# KegWasher_1_5_Schematic.net
KiCad netlist of a schematic drawn in EasyEDA
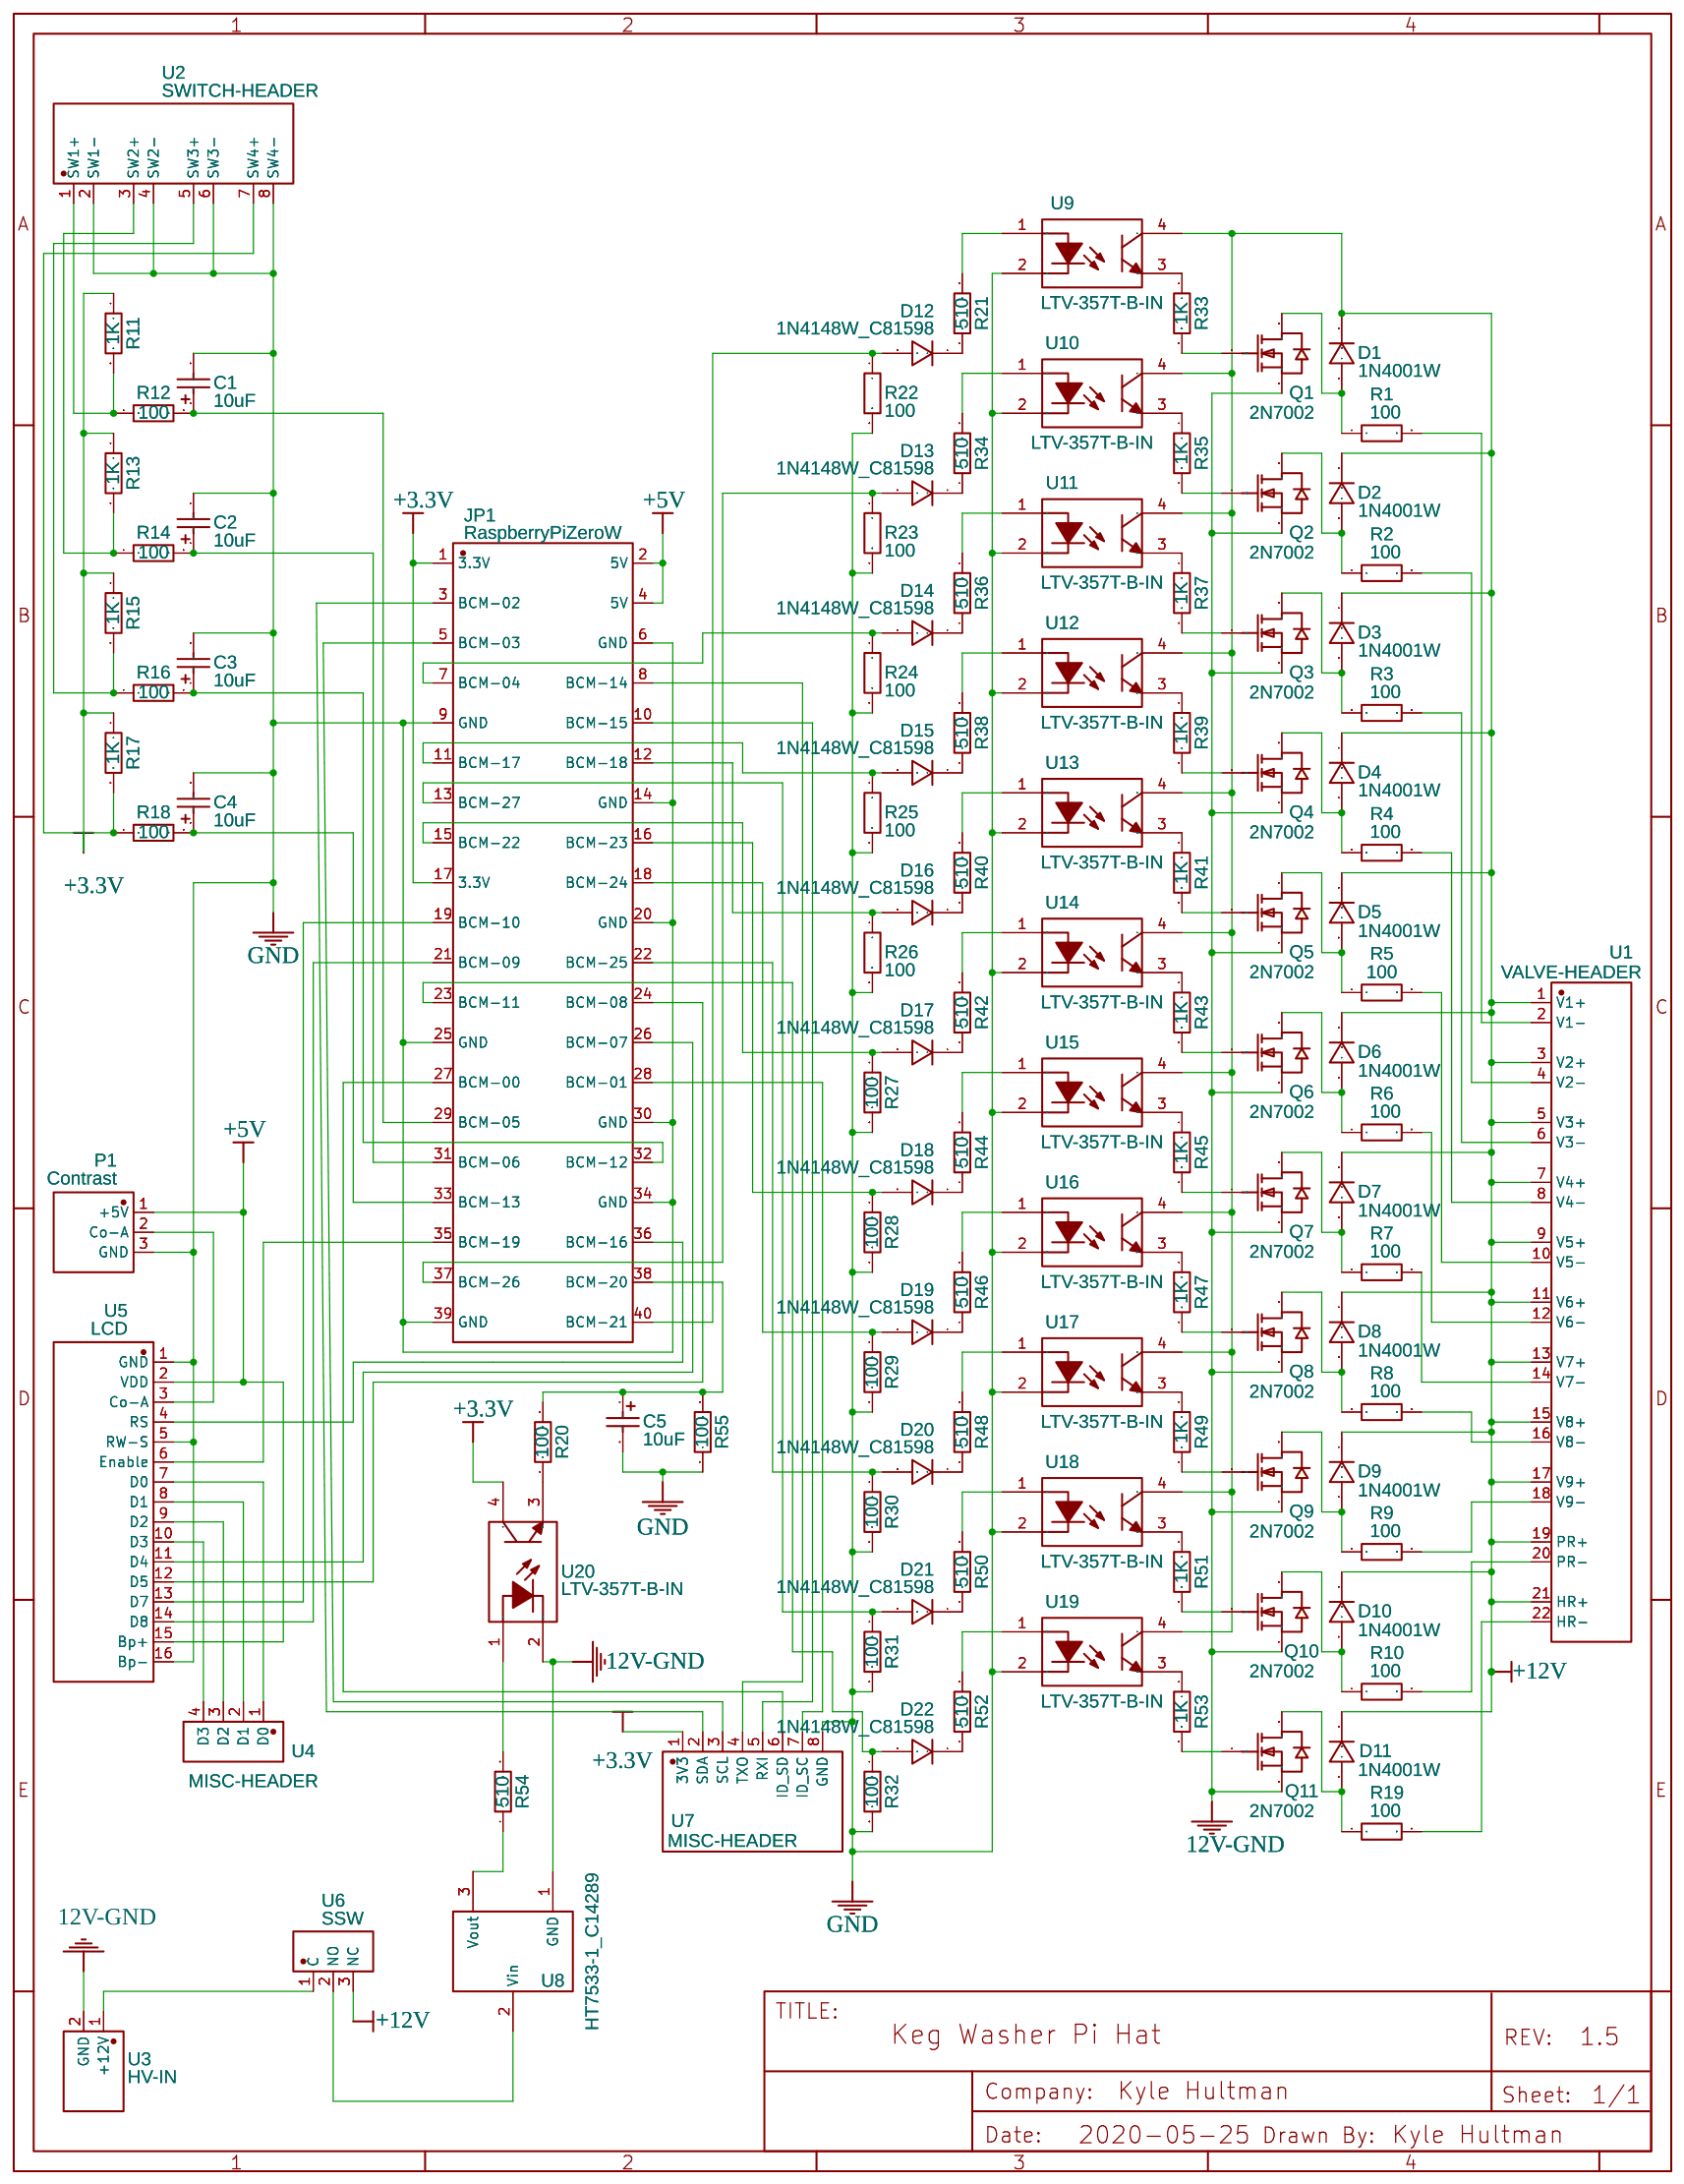
[diagram p0: schematic sheet]

(export (version "E")
  (design (tool "Eeschema 10.0.6"))
  (components
    (comp (ref "C1")
      (value "10uF")
      (fields
        (field (name "BOM_Manufacturer Part") "TAJA106K016RNJ")
        (field (name "BOM_Supplier Part") "C7171")
      )
      (libsource (lib "") (part "TAJA106K016RNJ"))
    )
    (comp (ref "C2")
      (value "10uF")
      (fields
        (field (name "BOM_Manufacturer Part") "TAJA106K016RNJ")
        (field (name "BOM_Supplier Part") "C7171")
      )
      (libsource (lib "") (part "TAJA106K016RNJ"))
    )
    (comp (ref "C3")
      (value "10uF")
      (fields
        (field (name "BOM_Manufacturer Part") "TAJA106K016RNJ")
        (field (name "BOM_Supplier Part") "C7171")
      )
      (libsource (lib "") (part "TAJA106K016RNJ"))
    )
    (comp (ref "C4")
      (value "10uF")
      (fields
        (field (name "BOM_Manufacturer Part") "TAJA106K016RNJ")
        (field (name "BOM_Supplier Part") "C7171")
      )
      (libsource (lib "") (part "TAJA106K016RNJ"))
    )
    (comp (ref "C5")
      (value "10uF")
      (fields
        (field (name "BOM_Manufacturer Part") "TAJA106K016RNJ")
        (field (name "BOM_Supplier Part") "C7171")
      )
      (libsource (lib "") (part "TAJA106K016RNJ_1"))
    )
    (comp (ref "D1")
      (value "1N4001W")
      (fields (field (name "BOM_Supplier Part") "C162732"))
      (libsource (lib "") (part "1N4001W"))
    )
    (comp (ref "D2")
      (value "1N4001W")
      (fields (field (name "BOM_Supplier Part") "C162732"))
      (libsource (lib "") (part "1N4001W"))
    )
    (comp (ref "D3")
      (value "1N4001W")
      (fields (field (name "BOM_Supplier Part") "C162732"))
      (libsource (lib "") (part "1N4001W"))
    )
    (comp (ref "D4")
      (value "1N4001W")
      (fields (field (name "BOM_Supplier Part") "C162732"))
      (libsource (lib "") (part "1N4001W"))
    )
    (comp (ref "D5")
      (value "1N4001W")
      (fields (field (name "BOM_Supplier Part") "C162732"))
      (libsource (lib "") (part "1N4001W"))
    )
    (comp (ref "D6")
      (value "1N4001W")
      (fields (field (name "BOM_Supplier Part") "C162732"))
      (libsource (lib "") (part "1N4001W"))
    )
    (comp (ref "D7")
      (value "1N4001W")
      (fields (field (name "BOM_Supplier Part") "C162732"))
      (libsource (lib "") (part "1N4001W"))
    )
    (comp (ref "D8")
      (value "1N4001W")
      (fields (field (name "BOM_Supplier Part") "C162732"))
      (libsource (lib "") (part "1N4001W"))
    )
    (comp (ref "D9")
      (value "1N4001W")
      (fields (field (name "BOM_Supplier Part") "C162732"))
      (libsource (lib "") (part "1N4001W"))
    )
    (comp (ref "D10")
      (value "1N4001W")
      (fields (field (name "BOM_Supplier Part") "C162732"))
      (libsource (lib "") (part "1N4001W"))
    )
    (comp (ref "D11")
      (value "1N4001W")
      (fields (field (name "BOM_Supplier Part") "C162732"))
      (libsource (lib "") (part "1N4001W"))
    )
    (comp (ref "D12")
      (value "1N4148W_C81598")
      (fields (field (name "BOM_Manufacturer Part") "1N4148W") (field (name "BOM_Supplier Part") "C81598"))
      (libsource (lib "") (part "1N4148W_C81598"))
    )
    (comp (ref "D13")
      (value "1N4148W_C81598")
      (fields (field (name "BOM_Manufacturer Part") "1N4148W") (field (name "BOM_Supplier Part") "C81598"))
      (libsource (lib "") (part "1N4148W_C81598"))
    )
    (comp (ref "D14")
      (value "1N4148W_C81598")
      (fields (field (name "BOM_Manufacturer Part") "1N4148W") (field (name "BOM_Supplier Part") "C81598"))
      (libsource (lib "") (part "1N4148W_C81598"))
    )
    (comp (ref "D15")
      (value "1N4148W_C81598")
      (fields (field (name "BOM_Manufacturer Part") "1N4148W") (field (name "BOM_Supplier Part") "C81598"))
      (libsource (lib "") (part "1N4148W_C81598"))
    )
    (comp (ref "D16")
      (value "1N4148W_C81598")
      (fields (field (name "BOM_Manufacturer Part") "1N4148W") (field (name "BOM_Supplier Part") "C81598"))
      (libsource (lib "") (part "1N4148W_C81598"))
    )
    (comp (ref "D17")
      (value "1N4148W_C81598")
      (fields (field (name "BOM_Manufacturer Part") "1N4148W") (field (name "BOM_Supplier Part") "C81598"))
      (libsource (lib "") (part "1N4148W_C81598"))
    )
    (comp (ref "D18")
      (value "1N4148W_C81598")
      (fields (field (name "BOM_Manufacturer Part") "1N4148W") (field (name "BOM_Supplier Part") "C81598"))
      (libsource (lib "") (part "1N4148W_C81598"))
    )
    (comp (ref "D19")
      (value "1N4148W_C81598")
      (fields (field (name "BOM_Manufacturer Part") "1N4148W") (field (name "BOM_Supplier Part") "C81598"))
      (libsource (lib "") (part "1N4148W_C81598"))
    )
    (comp (ref "D20")
      (value "1N4148W_C81598")
      (fields (field (name "BOM_Manufacturer Part") "1N4148W") (field (name "BOM_Supplier Part") "C81598"))
      (libsource (lib "") (part "1N4148W_C81598"))
    )
    (comp (ref "D21")
      (value "1N4148W_C81598")
      (fields (field (name "BOM_Manufacturer Part") "1N4148W") (field (name "BOM_Supplier Part") "C81598"))
      (libsource (lib "") (part "1N4148W_C81598"))
    )
    (comp (ref "D22")
      (value "1N4148W_C81598")
      (fields (field (name "BOM_Manufacturer Part") "1N4148W") (field (name "BOM_Supplier Part") "C81598"))
      (libsource (lib "") (part "1N4148W_C81598"))
    )
    (comp (ref "JP1") (value "RaspberryPiZeroW") (libsource (lib "") (part "RaspberryPiZeroW")))
    (comp (ref "P1") (value "Contrast") (libsource (lib "") (part "Contrast")))
    (comp (ref "Q1")
      (value "2N7002")
      (fields (field (name "BOM_Supplier Part") "C8545"))
      (libsource (lib "") (part "2N7002"))
    )
    (comp (ref "Q2")
      (value "2N7002")
      (fields (field (name "BOM_Supplier Part") "C8545"))
      (libsource (lib "") (part "2N7002"))
    )
    (comp (ref "Q3")
      (value "2N7002")
      (fields (field (name "BOM_Supplier Part") "C8545"))
      (libsource (lib "") (part "2N7002"))
    )
    (comp (ref "Q4")
      (value "2N7002")
      (fields (field (name "BOM_Supplier Part") "C8545"))
      (libsource (lib "") (part "2N7002"))
    )
    (comp (ref "Q5")
      (value "2N7002")
      (fields (field (name "BOM_Supplier Part") "C8545"))
      (libsource (lib "") (part "2N7002"))
    )
    (comp (ref "Q6")
      (value "2N7002")
      (fields (field (name "BOM_Supplier Part") "C8545"))
      (libsource (lib "") (part "2N7002"))
    )
    (comp (ref "Q7")
      (value "2N7002")
      (fields (field (name "BOM_Supplier Part") "C8545"))
      (libsource (lib "") (part "2N7002"))
    )
    (comp (ref "Q8")
      (value "2N7002")
      (fields (field (name "BOM_Supplier Part") "C8545"))
      (libsource (lib "") (part "2N7002"))
    )
    (comp (ref "Q9")
      (value "2N7002")
      (fields (field (name "BOM_Supplier Part") "C8545"))
      (libsource (lib "") (part "2N7002"))
    )
    (comp (ref "Q10")
      (value "2N7002")
      (fields (field (name "BOM_Supplier Part") "C8545"))
      (libsource (lib "") (part "2N7002"))
    )
    (comp (ref "Q11")
      (value "2N7002")
      (fields (field (name "BOM_Supplier Part") "C8545"))
      (libsource (lib "") (part "2N7002"))
    )
    (comp (ref "R1")
      (value "100")
      (fields
        (field (name "BOM_Manufacturer Part") "0805W8F1000T5E")
        (field (name "BOM_Supplier Part") "C17408")
      )
      (libsource (lib "") (part "0805W8F1000T5E"))
    )
    (comp (ref "R2")
      (value "100")
      (fields
        (field (name "BOM_Manufacturer Part") "0805W8F1000T5E")
        (field (name "BOM_Supplier Part") "C17408")
      )
      (libsource (lib "") (part "0805W8F1000T5E"))
    )
    (comp (ref "R3")
      (value "100")
      (fields
        (field (name "BOM_Manufacturer Part") "0805W8F1000T5E")
        (field (name "BOM_Supplier Part") "C17408")
      )
      (libsource (lib "") (part "0805W8F1000T5E"))
    )
    (comp (ref "R4")
      (value "100")
      (fields
        (field (name "BOM_Manufacturer Part") "0805W8F1000T5E")
        (field (name "BOM_Supplier Part") "C17408")
      )
      (libsource (lib "") (part "0805W8F1000T5E"))
    )
    (comp (ref "R5")
      (value "100")
      (fields
        (field (name "BOM_Manufacturer Part") "0805W8F1000T5E")
        (field (name "BOM_Supplier Part") "C17408")
      )
      (libsource (lib "") (part "0805W8F1000T5E"))
    )
    (comp (ref "R6")
      (value "100")
      (fields
        (field (name "BOM_Manufacturer Part") "0805W8F1000T5E")
        (field (name "BOM_Supplier Part") "C17408")
      )
      (libsource (lib "") (part "0805W8F1000T5E"))
    )
    (comp (ref "R7")
      (value "100")
      (fields
        (field (name "BOM_Manufacturer Part") "0805W8F1000T5E")
        (field (name "BOM_Supplier Part") "C17408")
      )
      (libsource (lib "") (part "0805W8F1000T5E"))
    )
    (comp (ref "R8")
      (value "100")
      (fields
        (field (name "BOM_Manufacturer Part") "0805W8F1000T5E")
        (field (name "BOM_Supplier Part") "C17408")
      )
      (libsource (lib "") (part "0805W8F1000T5E"))
    )
    (comp (ref "R9")
      (value "100")
      (fields
        (field (name "BOM_Manufacturer Part") "0805W8F1000T5E")
        (field (name "BOM_Supplier Part") "C17408")
      )
      (libsource (lib "") (part "0805W8F1000T5E"))
    )
    (comp (ref "R10")
      (value "100")
      (fields
        (field (name "BOM_Manufacturer Part") "0805W8F1000T5E")
        (field (name "BOM_Supplier Part") "C17408")
      )
      (libsource (lib "") (part "0805W8F1000T5E"))
    )
    (comp (ref "R11")
      (value "1K")
      (fields
        (field (name "BOM_Manufacturer Part") "0603WAF1001T5E")
        (field (name "BOM_Supplier Part") "C21190")
      )
      (libsource (lib "") (part "0603WAF1001T5E"))
    )
    (comp (ref "R12")
      (value "100")
      (fields
        (field (name "BOM_Manufacturer Part") "0805W8F1000T5E")
        (field (name "BOM_Supplier Part") "C17408")
      )
      (libsource (lib "") (part "0805W8F1000T5E"))
    )
    (comp (ref "R13")
      (value "1K")
      (fields
        (field (name "BOM_Manufacturer Part") "0603WAF1001T5E")
        (field (name "BOM_Supplier Part") "C21190")
      )
      (libsource (lib "") (part "0603WAF1001T5E"))
    )
    (comp (ref "R14")
      (value "100")
      (fields
        (field (name "BOM_Manufacturer Part") "0805W8F1000T5E")
        (field (name "BOM_Supplier Part") "C17408")
      )
      (libsource (lib "") (part "0805W8F1000T5E"))
    )
    (comp (ref "R15")
      (value "1K")
      (fields
        (field (name "BOM_Manufacturer Part") "0603WAF1001T5E")
        (field (name "BOM_Supplier Part") "C21190")
      )
      (libsource (lib "") (part "0603WAF1001T5E"))
    )
    (comp (ref "R16")
      (value "100")
      (fields
        (field (name "BOM_Manufacturer Part") "0805W8F1000T5E")
        (field (name "BOM_Supplier Part") "C17408")
      )
      (libsource (lib "") (part "0805W8F1000T5E"))
    )
    (comp (ref "R17")
      (value "1K")
      (fields
        (field (name "BOM_Manufacturer Part") "0603WAF1001T5E")
        (field (name "BOM_Supplier Part") "C21190")
      )
      (libsource (lib "") (part "0603WAF1001T5E"))
    )
    (comp (ref "R18")
      (value "100")
      (fields
        (field (name "BOM_Manufacturer Part") "0805W8F1000T5E")
        (field (name "BOM_Supplier Part") "C17408")
      )
      (libsource (lib "") (part "0805W8F1000T5E"))
    )
    (comp (ref "R19")
      (value "100")
      (fields
        (field (name "BOM_Manufacturer Part") "0805W8F1000T5E")
        (field (name "BOM_Supplier Part") "C17408")
      )
      (libsource (lib "") (part "0805W8F1000T5E"))
    )
    (comp (ref "R20")
      (value "100")
      (fields
        (field (name "BOM_Manufacturer Part") "0805W8F1000T5E")
        (field (name "BOM_Supplier Part") "C17408")
      )
      (libsource (lib "") (part "0805W8F1000T5E_1"))
    )
    (comp (ref "R21")
      (value "510")
      (fields
        (field (name "BOM_Manufacturer Part") "0603WAF5100T5E")
        (field (name "BOM_Supplier Part") "C23193")
      )
      (libsource (lib "") (part "0603WAF5100T5E"))
    )
    (comp (ref "R22")
      (value "100")
      (fields
        (field (name "BOM_Manufacturer Part") "0805W8F1000T5E")
        (field (name "BOM_Supplier Part") "C17408")
      )
      (libsource (lib "") (part "0805W8F1000T5E_2"))
    )
    (comp (ref "R23")
      (value "100")
      (fields
        (field (name "BOM_Manufacturer Part") "0805W8F1000T5E")
        (field (name "BOM_Supplier Part") "C17408")
      )
      (libsource (lib "") (part "0805W8F1000T5E_2"))
    )
    (comp (ref "R24")
      (value "100")
      (fields
        (field (name "BOM_Manufacturer Part") "0805W8F1000T5E")
        (field (name "BOM_Supplier Part") "C17408")
      )
      (libsource (lib "") (part "0805W8F1000T5E_2"))
    )
    (comp (ref "R25")
      (value "100")
      (fields
        (field (name "BOM_Manufacturer Part") "0805W8F1000T5E")
        (field (name "BOM_Supplier Part") "C17408")
      )
      (libsource (lib "") (part "0805W8F1000T5E_2"))
    )
    (comp (ref "R26")
      (value "100")
      (fields
        (field (name "BOM_Manufacturer Part") "0805W8F1000T5E")
        (field (name "BOM_Supplier Part") "C17408")
      )
      (libsource (lib "") (part "0805W8F1000T5E_2"))
    )
    (comp (ref "R27")
      (value "100")
      (fields
        (field (name "BOM_Manufacturer Part") "0805W8F1000T5E")
        (field (name "BOM_Supplier Part") "C17408")
      )
      (libsource (lib "") (part "0805W8F1000T5E_2"))
    )
    (comp (ref "R28")
      (value "100")
      (fields
        (field (name "BOM_Manufacturer Part") "0805W8F1000T5E")
        (field (name "BOM_Supplier Part") "C17408")
      )
      (libsource (lib "") (part "0805W8F1000T5E_2"))
    )
    (comp (ref "R29")
      (value "100")
      (fields
        (field (name "BOM_Manufacturer Part") "0805W8F1000T5E")
        (field (name "BOM_Supplier Part") "C17408")
      )
      (libsource (lib "") (part "0805W8F1000T5E_2"))
    )
    (comp (ref "R30")
      (value "100")
      (fields
        (field (name "BOM_Manufacturer Part") "0805W8F1000T5E")
        (field (name "BOM_Supplier Part") "C17408")
      )
      (libsource (lib "") (part "0805W8F1000T5E_2"))
    )
    (comp (ref "R31")
      (value "100")
      (fields
        (field (name "BOM_Manufacturer Part") "0805W8F1000T5E")
        (field (name "BOM_Supplier Part") "C17408")
      )
      (libsource (lib "") (part "0805W8F1000T5E_2"))
    )
    (comp (ref "R32")
      (value "100")
      (fields
        (field (name "BOM_Manufacturer Part") "0805W8F1000T5E")
        (field (name "BOM_Supplier Part") "C17408")
      )
      (libsource (lib "") (part "0805W8F1000T5E_2"))
    )
    (comp (ref "R33")
      (value "1K")
      (fields
        (field (name "BOM_Manufacturer Part") "0603WAF1001T5E")
        (field (name "BOM_Supplier Part") "C21190")
      )
      (libsource (lib "") (part "0603WAF1001T5E"))
    )
    (comp (ref "R34")
      (value "510")
      (fields
        (field (name "BOM_Manufacturer Part") "0603WAF5100T5E")
        (field (name "BOM_Supplier Part") "C23193")
      )
      (libsource (lib "") (part "0603WAF5100T5E"))
    )
    (comp (ref "R35")
      (value "1K")
      (fields
        (field (name "BOM_Manufacturer Part") "0603WAF1001T5E")
        (field (name "BOM_Supplier Part") "C21190")
      )
      (libsource (lib "") (part "0603WAF1001T5E"))
    )
    (comp (ref "R36")
      (value "510")
      (fields
        (field (name "BOM_Manufacturer Part") "0603WAF5100T5E")
        (field (name "BOM_Supplier Part") "C23193")
      )
      (libsource (lib "") (part "0603WAF5100T5E"))
    )
    (comp (ref "R37")
      (value "1K")
      (fields
        (field (name "BOM_Manufacturer Part") "0603WAF1001T5E")
        (field (name "BOM_Supplier Part") "C21190")
      )
      (libsource (lib "") (part "0603WAF1001T5E"))
    )
    (comp (ref "R38")
      (value "510")
      (fields
        (field (name "BOM_Manufacturer Part") "0603WAF5100T5E")
        (field (name "BOM_Supplier Part") "C23193")
      )
      (libsource (lib "") (part "0603WAF5100T5E"))
    )
    (comp (ref "R39")
      (value "1K")
      (fields
        (field (name "BOM_Manufacturer Part") "0603WAF1001T5E")
        (field (name "BOM_Supplier Part") "C21190")
      )
      (libsource (lib "") (part "0603WAF1001T5E"))
    )
    (comp (ref "R40")
      (value "510")
      (fields
        (field (name "BOM_Manufacturer Part") "0603WAF5100T5E")
        (field (name "BOM_Supplier Part") "C23193")
      )
      (libsource (lib "") (part "0603WAF5100T5E"))
    )
    (comp (ref "R41")
      (value "1K")
      (fields
        (field (name "BOM_Manufacturer Part") "0603WAF1001T5E")
        (field (name "BOM_Supplier Part") "C21190")
      )
      (libsource (lib "") (part "0603WAF1001T5E"))
    )
    (comp (ref "R42")
      (value "510")
      (fields
        (field (name "BOM_Manufacturer Part") "0603WAF5100T5E")
        (field (name "BOM_Supplier Part") "C23193")
      )
      (libsource (lib "") (part "0603WAF5100T5E"))
    )
    (comp (ref "R43")
      (value "1K")
      (fields
        (field (name "BOM_Manufacturer Part") "0603WAF1001T5E")
        (field (name "BOM_Supplier Part") "C21190")
      )
      (libsource (lib "") (part "0603WAF1001T5E"))
    )
    (comp (ref "R44")
      (value "510")
      (fields
        (field (name "BOM_Manufacturer Part") "0603WAF5100T5E")
        (field (name "BOM_Supplier Part") "C23193")
      )
      (libsource (lib "") (part "0603WAF5100T5E"))
    )
    (comp (ref "R45")
      (value "1K")
      (fields
        (field (name "BOM_Manufacturer Part") "0603WAF1001T5E")
        (field (name "BOM_Supplier Part") "C21190")
      )
      (libsource (lib "") (part "0603WAF1001T5E"))
    )
    (comp (ref "R46")
      (value "510")
      (fields
        (field (name "BOM_Manufacturer Part") "0603WAF5100T5E")
        (field (name "BOM_Supplier Part") "C23193")
      )
      (libsource (lib "") (part "0603WAF5100T5E"))
    )
    (comp (ref "R47")
      (value "1K")
      (fields
        (field (name "BOM_Manufacturer Part") "0603WAF1001T5E")
        (field (name "BOM_Supplier Part") "C21190")
      )
      (libsource (lib "") (part "0603WAF1001T5E"))
    )
    (comp (ref "R48")
      (value "510")
      (fields
        (field (name "BOM_Manufacturer Part") "0603WAF5100T5E")
        (field (name "BOM_Supplier Part") "C23193")
      )
      (libsource (lib "") (part "0603WAF5100T5E"))
    )
    (comp (ref "R49")
      (value "1K")
      (fields
        (field (name "BOM_Manufacturer Part") "0603WAF1001T5E")
        (field (name "BOM_Supplier Part") "C21190")
      )
      (libsource (lib "") (part "0603WAF1001T5E"))
    )
    (comp (ref "R50")
      (value "510")
      (fields
        (field (name "BOM_Manufacturer Part") "0603WAF5100T5E")
        (field (name "BOM_Supplier Part") "C23193")
      )
      (libsource (lib "") (part "0603WAF5100T5E"))
    )
    (comp (ref "R51")
      (value "1K")
      (fields
        (field (name "BOM_Manufacturer Part") "0603WAF1001T5E")
        (field (name "BOM_Supplier Part") "C21190")
      )
      (libsource (lib "") (part "0603WAF1001T5E"))
    )
    (comp (ref "R52")
      (value "510")
      (fields
        (field (name "BOM_Manufacturer Part") "0603WAF5100T5E")
        (field (name "BOM_Supplier Part") "C23193")
      )
      (libsource (lib "") (part "0603WAF5100T5E"))
    )
    (comp (ref "R53")
      (value "1K")
      (fields
        (field (name "BOM_Manufacturer Part") "0603WAF1001T5E")
        (field (name "BOM_Supplier Part") "C21190")
      )
      (libsource (lib "") (part "0603WAF1001T5E"))
    )
    (comp (ref "R54")
      (value "510")
      (fields
        (field (name "BOM_Manufacturer Part") "0603WAF5100T5E")
        (field (name "BOM_Supplier Part") "C23193")
      )
      (libsource (lib "") (part "0603WAF5100T5E"))
    )
    (comp (ref "R55")
      (value "100")
      (fields
        (field (name "BOM_Manufacturer Part") "0805W8F1000T5E")
        (field (name "BOM_Supplier Part") "C17408")
      )
      (libsource (lib "") (part "0805W8F1000T5E_1"))
    )
    (comp (ref "U1") (value "VALVE-HEADER") (libsource (lib "") (part "VALVE-HEADER")))
    (comp (ref "U2") (value "SWITCH-HEADER") (libsource (lib "") (part "SWITCH-HEADER")))
    (comp (ref "U3") (value "HV-IN") (libsource (lib "") (part "HV-IN")))
    (comp (ref "U4") (value "MISC-HEADER") (libsource (lib "") (part "MISC-HEADER")))
    (comp (ref "U5") (value "LCD") (libsource (lib "") (part "LCD")))
    (comp (ref "U6") (value "SSW") (libsource (lib "") (part "SSW")))
    (comp (ref "U7") (value "MISC-HEADER") (libsource (lib "") (part "MISC-HEADER_1")))
    (comp (ref "U8")
      (value "HT7533-1_C14289")
      (fields (field (name "BOM_Manufacturer Part") "HT7533-1") (field (name "BOM_Supplier Part") "C14289"))
      (libsource (lib "") (part "HT7533-1_C14289"))
    )
    (comp (ref "U9")
      (value "LTV-357T-B-IN")
      (fields (field (name "BOM_Supplier Part") "C406713"))
      (libsource (lib "") (part "LTV-357T-B-IN"))
    )
    (comp (ref "U10")
      (value "LTV-357T-B-IN")
      (fields (field (name "BOM_Supplier Part") "C406713"))
      (libsource (lib "") (part "LTV-357T-B-IN"))
    )
    (comp (ref "U11")
      (value "LTV-357T-B-IN")
      (fields (field (name "BOM_Supplier Part") "C406713"))
      (libsource (lib "") (part "LTV-357T-B-IN"))
    )
    (comp (ref "U12")
      (value "LTV-357T-B-IN")
      (fields (field (name "BOM_Supplier Part") "C406713"))
      (libsource (lib "") (part "LTV-357T-B-IN"))
    )
    (comp (ref "U13")
      (value "LTV-357T-B-IN")
      (fields (field (name "BOM_Supplier Part") "C406713"))
      (libsource (lib "") (part "LTV-357T-B-IN"))
    )
    (comp (ref "U14")
      (value "LTV-357T-B-IN")
      (fields (field (name "BOM_Supplier Part") "C406713"))
      (libsource (lib "") (part "LTV-357T-B-IN"))
    )
    (comp (ref "U15")
      (value "LTV-357T-B-IN")
      (fields (field (name "BOM_Supplier Part") "C406713"))
      (libsource (lib "") (part "LTV-357T-B-IN"))
    )
    (comp (ref "U16")
      (value "LTV-357T-B-IN")
      (fields (field (name "BOM_Supplier Part") "C406713"))
      (libsource (lib "") (part "LTV-357T-B-IN"))
    )
    (comp (ref "U17")
      (value "LTV-357T-B-IN")
      (fields (field (name "BOM_Supplier Part") "C406713"))
      (libsource (lib "") (part "LTV-357T-B-IN"))
    )
    (comp (ref "U18")
      (value "LTV-357T-B-IN")
      (fields (field (name "BOM_Supplier Part") "C406713"))
      (libsource (lib "") (part "LTV-357T-B-IN"))
    )
    (comp (ref "U19")
      (value "LTV-357T-B-IN")
      (fields (field (name "BOM_Supplier Part") "C406713"))
      (libsource (lib "") (part "LTV-357T-B-IN"))
    )
    (comp (ref "U20")
      (value "LTV-357T-B-IN")
      (fields (field (name "BOM_Supplier Part") "C406713"))
      (libsource (lib "") (part "LTV-357T-B-IN_1"))
    )
  )
  (nets
    (net (code "1") (name "+3.3V") (class "Default")
      (node (ref "JP1") (pin "1") (pinfunction "3.3V_1") (pintype "unspecified"))
      (node (ref "JP1") (pin "17") (pinfunction "3.3V_17") (pintype "unspecified"))
      (node (ref "R11") (pin "1") (pinfunction "1_1") (pintype "input"))
      (node (ref "R13") (pin "1") (pinfunction "1_1") (pintype "input"))
      (node (ref "R15") (pin "1") (pinfunction "1_1") (pintype "input"))
      (node (ref "R17") (pin "1") (pinfunction "1_1") (pintype "input"))
      (node (ref "U20") (pin "4") (pinfunction "4_4") (pintype "unspecified"))
      (node (ref "U7") (pin "1") (pinfunction "3V3_1") (pintype "unspecified"))
    )
    (net (code "2") (name "+5V") (class "Default")
      (node (ref "JP1") (pin "2") (pinfunction "5V_2") (pintype "unspecified"))
      (node (ref "JP1") (pin "4") (pinfunction "5V_4") (pintype "unspecified"))
      (node (ref "P1") (pin "1") (pinfunction "+5V_1") (pintype "unspecified"))
      (node (ref "U5") (pin "15") (pinfunction "Bp+_15") (pintype "unspecified"))
      (node (ref "U5") (pin "2") (pinfunction "VDD_2") (pintype "unspecified"))
    )
    (net (code "3") (name "+12V") (class "Default")
      (node (ref "D1") (pin "1") (pinfunction "C_1") (pintype "unspecified"))
      (node (ref "D10") (pin "1") (pinfunction "C_1") (pintype "unspecified"))
      (node (ref "D11") (pin "1") (pinfunction "C_1") (pintype "unspecified"))
      (node (ref "D2") (pin "1") (pinfunction "C_1") (pintype "unspecified"))
      (node (ref "D3") (pin "1") (pinfunction "C_1") (pintype "unspecified"))
      (node (ref "D4") (pin "1") (pinfunction "C_1") (pintype "unspecified"))
      (node (ref "D5") (pin "1") (pinfunction "C_1") (pintype "unspecified"))
      (node (ref "D6") (pin "1") (pinfunction "C_1") (pintype "unspecified"))
      (node (ref "D7") (pin "1") (pinfunction "C_1") (pintype "unspecified"))
      (node (ref "D8") (pin "1") (pinfunction "C_1") (pintype "unspecified"))
      (node (ref "D9") (pin "1") (pinfunction "C_1") (pintype "unspecified"))
      (node (ref "U1") (pin "1") (pinfunction "V1+_1") (pintype "unspecified"))
      (node (ref "U1") (pin "11") (pinfunction "V6+_11") (pintype "unspecified"))
      (node (ref "U1") (pin "13") (pinfunction "V7+_13") (pintype "unspecified"))
      (node (ref "U1") (pin "15") (pinfunction "V8+_15") (pintype "unspecified"))
      (node (ref "U1") (pin "17") (pinfunction "V9+_17") (pintype "unspecified"))
      (node (ref "U1") (pin "19") (pinfunction "PR+_19") (pintype "unspecified"))
      (node (ref "U1") (pin "21") (pinfunction "HR+_21") (pintype "unspecified"))
      (node (ref "U1") (pin "3") (pinfunction "V2+_3") (pintype "unspecified"))
      (node (ref "U1") (pin "5") (pinfunction "V3+_5") (pintype "unspecified"))
      (node (ref "U1") (pin "7") (pinfunction "V4+_7") (pintype "unspecified"))
      (node (ref "U1") (pin "9") (pinfunction "V5+_9") (pintype "unspecified"))
      (node (ref "U10") (pin "4") (pinfunction "4_4") (pintype "unspecified"))
      (node (ref "U11") (pin "4") (pinfunction "4_4") (pintype "unspecified"))
      (node (ref "U12") (pin "4") (pinfunction "4_4") (pintype "unspecified"))
      (node (ref "U13") (pin "4") (pinfunction "4_4") (pintype "unspecified"))
      (node (ref "U14") (pin "4") (pinfunction "4_4") (pintype "unspecified"))
      (node (ref "U15") (pin "4") (pinfunction "4_4") (pintype "unspecified"))
      (node (ref "U16") (pin "4") (pinfunction "4_4") (pintype "unspecified"))
      (node (ref "U17") (pin "4") (pinfunction "4_4") (pintype "unspecified"))
      (node (ref "U18") (pin "4") (pinfunction "4_4") (pintype "unspecified"))
      (node (ref "U19") (pin "4") (pinfunction "4_4") (pintype "unspecified"))
      (node (ref "U6") (pin "3") (pinfunction "NC_3") (pintype "unspecified"))
      (node (ref "U9") (pin "4") (pinfunction "4_4") (pintype "unspecified"))
    )
    (net (code "4") (name "12V-GND") (class "Default")
      (node (ref "Q1") (pin "2") (pinfunction "S_2") (pintype "unspecified"))
      (node (ref "Q10") (pin "2") (pinfunction "S_2") (pintype "unspecified"))
      (node (ref "Q11") (pin "2") (pinfunction "S_2") (pintype "unspecified"))
      (node (ref "Q2") (pin "2") (pinfunction "S_2") (pintype "unspecified"))
      (node (ref "Q3") (pin "2") (pinfunction "S_2") (pintype "unspecified"))
      (node (ref "Q4") (pin "2") (pinfunction "S_2") (pintype "unspecified"))
      (node (ref "Q5") (pin "2") (pinfunction "S_2") (pintype "unspecified"))
      (node (ref "Q6") (pin "2") (pinfunction "S_2") (pintype "unspecified"))
      (node (ref "Q7") (pin "2") (pinfunction "S_2") (pintype "unspecified"))
      (node (ref "Q8") (pin "2") (pinfunction "S_2") (pintype "unspecified"))
      (node (ref "Q9") (pin "2") (pinfunction "S_2") (pintype "unspecified"))
      (node (ref "U20") (pin "2") (pinfunction "2_2") (pintype "unspecified"))
      (node (ref "U3") (pin "2") (pinfunction "GND_2") (pintype "unspecified"))
      (node (ref "U8") (pin "1") (pinfunction "GND_1") (pintype "unspecified"))
    )
    (net (code "5") (name "GND") (class "Default")
      (node (ref "C1") (pin "2") (pinfunction "2_2") (pintype "input"))
      (node (ref "C2") (pin "2") (pinfunction "2_2") (pintype "input"))
      (node (ref "C3") (pin "2") (pinfunction "2_2") (pintype "input"))
      (node (ref "C4") (pin "2") (pinfunction "2_2") (pintype "input"))
      (node (ref "C5") (pin "2") (pinfunction "2_2") (pintype "input"))
      (node (ref "JP1") (pin "14") (pinfunction "GND_14") (pintype "unspecified"))
      (node (ref "JP1") (pin "20") (pinfunction "GND_20") (pintype "unspecified"))
      (node (ref "JP1") (pin "25") (pinfunction "GND_25") (pintype "unspecified"))
      (node (ref "JP1") (pin "30") (pinfunction "GND_30") (pintype "unspecified"))
      (node (ref "JP1") (pin "34") (pinfunction "GND_34") (pintype "unspecified"))
      (node (ref "JP1") (pin "39") (pinfunction "GND_39") (pintype "unspecified"))
      (node (ref "JP1") (pin "6") (pinfunction "GND_6") (pintype "unspecified"))
      (node (ref "JP1") (pin "9") (pinfunction "GND_9") (pintype "unspecified"))
      (node (ref "P1") (pin "3") (pinfunction "GND_3") (pintype "unspecified"))
      (node (ref "R22") (pin "2") (pinfunction "2_2") (pintype "input"))
      (node (ref "R23") (pin "2") (pinfunction "2_2") (pintype "input"))
      (node (ref "R24") (pin "2") (pinfunction "2_2") (pintype "input"))
      (node (ref "R25") (pin "2") (pinfunction "2_2") (pintype "input"))
      (node (ref "R26") (pin "2") (pinfunction "2_2") (pintype "input"))
      (node (ref "R27") (pin "2") (pinfunction "2_2") (pintype "input"))
      (node (ref "R28") (pin "2") (pinfunction "2_2") (pintype "input"))
      (node (ref "R29") (pin "2") (pinfunction "2_2") (pintype "input"))
      (node (ref "R30") (pin "2") (pinfunction "2_2") (pintype "input"))
      (node (ref "R31") (pin "2") (pinfunction "2_2") (pintype "input"))
      (node (ref "R32") (pin "2") (pinfunction "2_2") (pintype "input"))
      (node (ref "R55") (pin "1") (pinfunction "1_1") (pintype "input"))
      (node (ref "U10") (pin "2") (pinfunction "2_2") (pintype "unspecified"))
      (node (ref "U11") (pin "2") (pinfunction "2_2") (pintype "unspecified"))
      (node (ref "U12") (pin "2") (pinfunction "2_2") (pintype "unspecified"))
      (node (ref "U13") (pin "2") (pinfunction "2_2") (pintype "unspecified"))
      (node (ref "U14") (pin "2") (pinfunction "2_2") (pintype "unspecified"))
      (node (ref "U15") (pin "2") (pinfunction "2_2") (pintype "unspecified"))
      (node (ref "U16") (pin "2") (pinfunction "2_2") (pintype "unspecified"))
      (node (ref "U17") (pin "2") (pinfunction "2_2") (pintype "unspecified"))
      (node (ref "U18") (pin "2") (pinfunction "2_2") (pintype "unspecified"))
      (node (ref "U19") (pin "2") (pinfunction "2_2") (pintype "unspecified"))
      (node (ref "U2") (pin "2") (pinfunction "SW1-_2") (pintype "unspecified"))
      (node (ref "U2") (pin "4") (pinfunction "SW2-_4") (pintype "unspecified"))
      (node (ref "U2") (pin "6") (pinfunction "SW3-_6") (pintype "unspecified"))
      (node (ref "U2") (pin "8") (pinfunction "SW4-_8") (pintype "unspecified"))
      (node (ref "U5") (pin "1") (pinfunction "GND_1") (pintype "unspecified"))
      (node (ref "U5") (pin "16") (pinfunction "Bp-_16") (pintype "unspecified"))
      (node (ref "U5") (pin "5") (pinfunction "RW-S_5") (pintype "unspecified"))
      (node (ref "U7") (pin "8") (pinfunction "GND_8") (pintype "unspecified"))
      (node (ref "U9") (pin "2") (pinfunction "2_2") (pintype "unspecified"))
    )
    (net (code "6") (name "Net-(D1-A)") (class "Default")
      (node (ref "D1") (pin "2") (pinfunction "A_2") (pintype "unspecified"))
      (node (ref "Q1") (pin "3") (pinfunction "D_3") (pintype "unspecified"))
      (node (ref "R1") (pin "1") (pinfunction "1_1") (pintype "input"))
    )
    (net (code "7") (name "Net-(D2-A)") (class "Default")
      (node (ref "D2") (pin "2") (pinfunction "A_2") (pintype "unspecified"))
      (node (ref "Q2") (pin "3") (pinfunction "D_3") (pintype "unspecified"))
      (node (ref "R2") (pin "1") (pinfunction "1_1") (pintype "input"))
    )
    (net (code "8") (name "Net-(D3-A)") (class "Default")
      (node (ref "D3") (pin "2") (pinfunction "A_2") (pintype "unspecified"))
      (node (ref "Q3") (pin "3") (pinfunction "D_3") (pintype "unspecified"))
      (node (ref "R3") (pin "1") (pinfunction "1_1") (pintype "input"))
    )
    (net (code "9") (name "Net-(D4-A)") (class "Default")
      (node (ref "D4") (pin "2") (pinfunction "A_2") (pintype "unspecified"))
      (node (ref "Q4") (pin "3") (pinfunction "D_3") (pintype "unspecified"))
      (node (ref "R4") (pin "1") (pinfunction "1_1") (pintype "input"))
    )
    (net (code "10") (name "Net-(D5-A)") (class "Default")
      (node (ref "D5") (pin "2") (pinfunction "A_2") (pintype "unspecified"))
      (node (ref "Q5") (pin "3") (pinfunction "D_3") (pintype "unspecified"))
      (node (ref "R5") (pin "1") (pinfunction "1_1") (pintype "input"))
    )
    (net (code "11") (name "Net-(D6-A)") (class "Default")
      (node (ref "D6") (pin "2") (pinfunction "A_2") (pintype "unspecified"))
      (node (ref "Q6") (pin "3") (pinfunction "D_3") (pintype "unspecified"))
      (node (ref "R6") (pin "1") (pinfunction "1_1") (pintype "input"))
    )
    (net (code "12") (name "Net-(D7-A)") (class "Default")
      (node (ref "D7") (pin "2") (pinfunction "A_2") (pintype "unspecified"))
      (node (ref "Q7") (pin "3") (pinfunction "D_3") (pintype "unspecified"))
      (node (ref "R7") (pin "1") (pinfunction "1_1") (pintype "input"))
    )
    (net (code "13") (name "Net-(D8-A)") (class "Default")
      (node (ref "D8") (pin "2") (pinfunction "A_2") (pintype "unspecified"))
      (node (ref "Q8") (pin "3") (pinfunction "D_3") (pintype "unspecified"))
      (node (ref "R8") (pin "1") (pinfunction "1_1") (pintype "input"))
    )
    (net (code "14") (name "Net-(D9-A)") (class "Default")
      (node (ref "D9") (pin "2") (pinfunction "A_2") (pintype "unspecified"))
      (node (ref "Q9") (pin "3") (pinfunction "D_3") (pintype "unspecified"))
      (node (ref "R9") (pin "1") (pinfunction "1_1") (pintype "input"))
    )
    (net (code "15") (name "Net-(D10-A)") (class "Default")
      (node (ref "D10") (pin "2") (pinfunction "A_2") (pintype "unspecified"))
      (node (ref "Q10") (pin "3") (pinfunction "D_3") (pintype "unspecified"))
      (node (ref "R10") (pin "1") (pinfunction "1_1") (pintype "input"))
    )
    (net (code "16") (name "Net-(D11-A)") (class "Default")
      (node (ref "D11") (pin "2") (pinfunction "A_2") (pintype "unspecified"))
      (node (ref "Q11") (pin "3") (pinfunction "D_3") (pintype "unspecified"))
      (node (ref "R19") (pin "1") (pinfunction "1_1") (pintype "input"))
    )
    (net (code "17") (name "Net-(D12-A)") (class "Default")
      (node (ref "D12") (pin "2") (pinfunction "A_2") (pintype "unspecified"))
      (node (ref "JP1") (pin "40") (pinfunction "BCM-21_40") (pintype "unspecified"))
      (node (ref "R22") (pin "1") (pinfunction "1_1") (pintype "input"))
    )
    (net (code "18") (name "Net-(D12-K)") (class "Default")
      (node (ref "D12") (pin "1") (pinfunction "K_1") (pintype "unspecified"))
      (node (ref "R21") (pin "1") (pinfunction "1_1") (pintype "input"))
    )
    (net (code "19") (name "Net-(D13-A)") (class "Default")
      (node (ref "D13") (pin "2") (pinfunction "A_2") (pintype "unspecified"))
      (node (ref "JP1") (pin "37") (pinfunction "BCM-26_37") (pintype "unspecified"))
      (node (ref "R23") (pin "1") (pinfunction "1_1") (pintype "input"))
    )
    (net (code "20") (name "Net-(D13-K)") (class "Default")
      (node (ref "D13") (pin "1") (pinfunction "K_1") (pintype "unspecified"))
      (node (ref "R34") (pin "1") (pinfunction "1_1") (pintype "input"))
    )
    (net (code "21") (name "Net-(D14-A)") (class "Default")
      (node (ref "D14") (pin "2") (pinfunction "A_2") (pintype "unspecified"))
      (node (ref "JP1") (pin "7") (pinfunction "BCM-04_7") (pintype "unspecified"))
      (node (ref "R24") (pin "1") (pinfunction "1_1") (pintype "input"))
    )
    (net (code "22") (name "Net-(D14-K)") (class "Default")
      (node (ref "D14") (pin "1") (pinfunction "K_1") (pintype "unspecified"))
      (node (ref "R36") (pin "1") (pinfunction "1_1") (pintype "input"))
    )
    (net (code "23") (name "Net-(D15-A)") (class "Default")
      (node (ref "D15") (pin "2") (pinfunction "A_2") (pintype "unspecified"))
      (node (ref "JP1") (pin "11") (pinfunction "BCM-17_11") (pintype "unspecified"))
      (node (ref "R25") (pin "1") (pinfunction "1_1") (pintype "input"))
    )
    (net (code "24") (name "Net-(D15-K)") (class "Default")
      (node (ref "D15") (pin "1") (pinfunction "K_1") (pintype "unspecified"))
      (node (ref "R38") (pin "1") (pinfunction "1_1") (pintype "input"))
    )
    (net (code "25") (name "Net-(D16-A)") (class "Default")
      (node (ref "D16") (pin "2") (pinfunction "A_2") (pintype "unspecified"))
      (node (ref "JP1") (pin "12") (pinfunction "BCM-18_12") (pintype "unspecified"))
      (node (ref "R26") (pin "1") (pinfunction "1_1") (pintype "input"))
    )
    (net (code "26") (name "Net-(D16-K)") (class "Default")
      (node (ref "D16") (pin "1") (pinfunction "K_1") (pintype "unspecified"))
      (node (ref "R40") (pin "1") (pinfunction "1_1") (pintype "input"))
    )
    (net (code "27") (name "Net-(D17-A)") (class "Default")
      (node (ref "D17") (pin "2") (pinfunction "A_2") (pintype "unspecified"))
      (node (ref "JP1") (pin "15") (pinfunction "BCM-22_15") (pintype "unspecified"))
      (node (ref "R27") (pin "1") (pinfunction "1_1") (pintype "input"))
    )
    (net (code "28") (name "Net-(D17-K)") (class "Default")
      (node (ref "D17") (pin "1") (pinfunction "K_1") (pintype "unspecified"))
      (node (ref "R42") (pin "1") (pinfunction "1_1") (pintype "input"))
    )
    (net (code "29") (name "Net-(D18-A)") (class "Default")
      (node (ref "D18") (pin "2") (pinfunction "A_2") (pintype "unspecified"))
      (node (ref "JP1") (pin "16") (pinfunction "BCM-23_16") (pintype "unspecified"))
      (node (ref "R28") (pin "1") (pinfunction "1_1") (pintype "input"))
    )
    (net (code "30") (name "Net-(D18-K)") (class "Default")
      (node (ref "D18") (pin "1") (pinfunction "K_1") (pintype "unspecified"))
      (node (ref "R44") (pin "1") (pinfunction "1_1") (pintype "input"))
    )
    (net (code "31") (name "Net-(D19-A)") (class "Default")
      (node (ref "D19") (pin "2") (pinfunction "A_2") (pintype "unspecified"))
      (node (ref "JP1") (pin "18") (pinfunction "BCM-24_18") (pintype "unspecified"))
      (node (ref "R29") (pin "1") (pinfunction "1_1") (pintype "input"))
    )
    (net (code "32") (name "Net-(D19-K)") (class "Default")
      (node (ref "D19") (pin "1") (pinfunction "K_1") (pintype "unspecified"))
      (node (ref "R46") (pin "1") (pinfunction "1_1") (pintype "input"))
    )
    (net (code "33") (name "Net-(D20-A)") (class "Default")
      (node (ref "D20") (pin "2") (pinfunction "A_2") (pintype "unspecified"))
      (node (ref "JP1") (pin "22") (pinfunction "BCM-25_22") (pintype "unspecified"))
      (node (ref "R30") (pin "1") (pinfunction "1_1") (pintype "input"))
    )
    (net (code "34") (name "Net-(D20-K)") (class "Default")
      (node (ref "D20") (pin "1") (pinfunction "K_1") (pintype "unspecified"))
      (node (ref "R48") (pin "1") (pinfunction "1_1") (pintype "input"))
    )
    (net (code "35") (name "Net-(D21-A)") (class "Default")
      (node (ref "D21") (pin "2") (pinfunction "A_2") (pintype "unspecified"))
      (node (ref "JP1") (pin "13") (pinfunction "BCM-27_13") (pintype "unspecified"))
      (node (ref "R31") (pin "1") (pinfunction "1_1") (pintype "input"))
    )
    (net (code "36") (name "Net-(D21-K)") (class "Default")
      (node (ref "D21") (pin "1") (pinfunction "K_1") (pintype "unspecified"))
      (node (ref "R50") (pin "1") (pinfunction "1_1") (pintype "input"))
    )
    (net (code "37") (name "Net-(D22-A)") (class "Default")
      (node (ref "D22") (pin "2") (pinfunction "A_2") (pintype "unspecified"))
      (node (ref "JP1") (pin "23") (pinfunction "BCM-11_23") (pintype "unspecified"))
      (node (ref "R32") (pin "1") (pinfunction "1_1") (pintype "input"))
    )
    (net (code "38") (name "Net-(D22-K)") (class "Default")
      (node (ref "D22") (pin "1") (pinfunction "K_1") (pintype "unspecified"))
      (node (ref "R52") (pin "1") (pinfunction "1_1") (pintype "input"))
    )
    (net (code "39") (name "Net-(JP1-BCM-00)") (class "Default")
      (node (ref "JP1") (pin "27") (pinfunction "BCM-00_27") (pintype "unspecified"))
      (node (ref "U7") (pin "6") (pinfunction "ID_SD_6") (pintype "unspecified"))
    )
    (net (code "40") (name "Net-(JP1-BCM-01)") (class "Default")
      (node (ref "JP1") (pin "28") (pinfunction "BCM-01_28") (pintype "unspecified"))
      (node (ref "U7") (pin "7") (pinfunction "ID_SC_7") (pintype "unspecified"))
    )
    (net (code "41") (name "Net-(JP1-BCM-02)") (class "Default")
      (node (ref "JP1") (pin "3") (pinfunction "BCM-02_3") (pintype "unspecified"))
      (node (ref "U7") (pin "2") (pinfunction "SDA_2") (pintype "unspecified"))
    )
    (net (code "42") (name "Net-(JP1-BCM-03)") (class "Default")
      (node (ref "JP1") (pin "5") (pinfunction "BCM-03_5") (pintype "unspecified"))
      (node (ref "U7") (pin "3") (pinfunction "SCL_3") (pintype "unspecified"))
    )
    (net (code "43") (name "Net-(JP1-BCM-05)") (class "Default")
      (node (ref "C1") (pin "1") (pinfunction "1_1") (pintype "input"))
      (node (ref "JP1") (pin "29") (pinfunction "BCM-05_29") (pintype "unspecified"))
      (node (ref "R12") (pin "2") (pinfunction "2_2") (pintype "input"))
    )
    (net (code "44") (name "Net-(JP1-BCM-06)") (class "Default")
      (node (ref "C2") (pin "1") (pinfunction "1_1") (pintype "input"))
      (node (ref "JP1") (pin "31") (pinfunction "BCM-06_31") (pintype "unspecified"))
      (node (ref "R14") (pin "2") (pinfunction "2_2") (pintype "input"))
    )
    (net (code "45") (name "Net-(JP1-BCM-07)") (class "Default")
      (node (ref "JP1") (pin "26") (pinfunction "BCM-07_26") (pintype "unspecified"))
      (node (ref "U5") (pin "11") (pinfunction "D4_11") (pintype "unspecified"))
    )
    (net (code "46") (name "Net-(JP1-BCM-08)") (class "Default")
      (node (ref "JP1") (pin "24") (pinfunction "BCM-08_24") (pintype "unspecified"))
      (node (ref "U5") (pin "12") (pinfunction "D5_12") (pintype "unspecified"))
    )
    (net (code "47") (name "Net-(JP1-BCM-09)") (class "Default")
      (node (ref "JP1") (pin "21") (pinfunction "BCM-09_21") (pintype "unspecified"))
      (node (ref "U5") (pin "14") (pinfunction "D8_14") (pintype "unspecified"))
    )
    (net (code "48") (name "Net-(JP1-BCM-10)") (class "Default")
      (node (ref "JP1") (pin "19") (pinfunction "BCM-10_19") (pintype "unspecified"))
      (node (ref "U5") (pin "13") (pinfunction "D7_13") (pintype "unspecified"))
    )
    (net (code "49") (name "Net-(JP1-BCM-12)") (class "Default")
      (node (ref "C3") (pin "1") (pinfunction "1_1") (pintype "input"))
      (node (ref "JP1") (pin "32") (pinfunction "BCM-12_32") (pintype "unspecified"))
      (node (ref "R16") (pin "2") (pinfunction "2_2") (pintype "input"))
    )
    (net (code "50") (name "Net-(JP1-BCM-13)") (class "Default")
      (node (ref "C4") (pin "1") (pinfunction "1_1") (pintype "input"))
      (node (ref "JP1") (pin "33") (pinfunction "BCM-13_33") (pintype "unspecified"))
      (node (ref "R18") (pin "2") (pinfunction "2_2") (pintype "input"))
    )
    (net (code "51") (name "Net-(JP1-BCM-14)") (class "Default")
      (node (ref "JP1") (pin "8") (pinfunction "BCM-14_8") (pintype "unspecified"))
      (node (ref "U7") (pin "4") (pinfunction "TXO_4") (pintype "unspecified"))
    )
    (net (code "52") (name "Net-(JP1-BCM-15)") (class "Default")
      (node (ref "JP1") (pin "10") (pinfunction "BCM-15_10") (pintype "unspecified"))
      (node (ref "U7") (pin "5") (pinfunction "RXI_5") (pintype "unspecified"))
    )
    (net (code "53") (name "Net-(JP1-BCM-16)") (class "Default")
      (node (ref "JP1") (pin "36") (pinfunction "BCM-16_36") (pintype "unspecified"))
      (node (ref "U5") (pin "4") (pinfunction "RS_4") (pintype "unspecified"))
    )
    (net (code "54") (name "Net-(JP1-BCM-19)") (class "Default")
      (node (ref "JP1") (pin "35") (pinfunction "BCM-19_35") (pintype "unspecified"))
      (node (ref "U5") (pin "6") (pinfunction "Enable_6") (pintype "unspecified"))
    )
    (net (code "55") (name "Net-(JP1-BCM-20)") (class "Default")
      (node (ref "C5") (pin "1") (pinfunction "1_1") (pintype "input"))
      (node (ref "JP1") (pin "38") (pinfunction "BCM-20_38") (pintype "unspecified"))
      (node (ref "R20") (pin "2") (pinfunction "2_2") (pintype "input"))
      (node (ref "R55") (pin "2") (pinfunction "2_2") (pintype "input"))
    )
    (net (code "56") (name "Net-(P1-Co-A)") (class "Default")
      (node (ref "P1") (pin "2") (pinfunction "Co-A_2") (pintype "unspecified"))
      (node (ref "U5") (pin "3") (pinfunction "Co-A_3") (pintype "unspecified"))
    )
    (net (code "57") (name "Net-(Q1-G)") (class "Default")
      (node (ref "Q1") (pin "1") (pinfunction "G_1") (pintype "unspecified"))
      (node (ref "R33") (pin "2") (pinfunction "2_2") (pintype "input"))
    )
    (net (code "58") (name "Net-(Q2-G)") (class "Default")
      (node (ref "Q2") (pin "1") (pinfunction "G_1") (pintype "unspecified"))
      (node (ref "R35") (pin "2") (pinfunction "2_2") (pintype "input"))
    )
    (net (code "59") (name "Net-(Q3-G)") (class "Default")
      (node (ref "Q3") (pin "1") (pinfunction "G_1") (pintype "unspecified"))
      (node (ref "R37") (pin "2") (pinfunction "2_2") (pintype "input"))
    )
    (net (code "60") (name "Net-(Q4-G)") (class "Default")
      (node (ref "Q4") (pin "1") (pinfunction "G_1") (pintype "unspecified"))
      (node (ref "R39") (pin "2") (pinfunction "2_2") (pintype "input"))
    )
    (net (code "61") (name "Net-(Q5-G)") (class "Default")
      (node (ref "Q5") (pin "1") (pinfunction "G_1") (pintype "unspecified"))
      (node (ref "R41") (pin "2") (pinfunction "2_2") (pintype "input"))
    )
    (net (code "62") (name "Net-(Q6-G)") (class "Default")
      (node (ref "Q6") (pin "1") (pinfunction "G_1") (pintype "unspecified"))
      (node (ref "R43") (pin "2") (pinfunction "2_2") (pintype "input"))
    )
    (net (code "63") (name "Net-(Q7-G)") (class "Default")
      (node (ref "Q7") (pin "1") (pinfunction "G_1") (pintype "unspecified"))
      (node (ref "R45") (pin "2") (pinfunction "2_2") (pintype "input"))
    )
    (net (code "64") (name "Net-(Q8-G)") (class "Default")
      (node (ref "Q8") (pin "1") (pinfunction "G_1") (pintype "unspecified"))
      (node (ref "R47") (pin "2") (pinfunction "2_2") (pintype "input"))
    )
    (net (code "65") (name "Net-(Q9-G)") (class "Default")
      (node (ref "Q9") (pin "1") (pinfunction "G_1") (pintype "unspecified"))
      (node (ref "R49") (pin "2") (pinfunction "2_2") (pintype "input"))
    )
    (net (code "66") (name "Net-(Q10-G)") (class "Default")
      (node (ref "Q10") (pin "1") (pinfunction "G_1") (pintype "unspecified"))
      (node (ref "R51") (pin "2") (pinfunction "2_2") (pintype "input"))
    )
    (net (code "67") (name "Net-(Q11-G)") (class "Default")
      (node (ref "Q11") (pin "1") (pinfunction "G_1") (pintype "unspecified"))
      (node (ref "R53") (pin "2") (pinfunction "2_2") (pintype "input"))
    )
    (net (code "68") (name "Net-(R20-Pad1)") (class "Default")
      (node (ref "R20") (pin "1") (pinfunction "1_1") (pintype "input"))
      (node (ref "U20") (pin "3") (pinfunction "3_3") (pintype "unspecified"))
    )
    (net (code "69") (name "Net-(R21-Pad2)") (class "Default")
      (node (ref "R21") (pin "2") (pinfunction "2_2") (pintype "input"))
      (node (ref "U9") (pin "1") (pinfunction "1_1") (pintype "unspecified"))
    )
    (net (code "70") (name "Net-(R33-Pad1)") (class "Default")
      (node (ref "R33") (pin "1") (pinfunction "1_1") (pintype "input"))
      (node (ref "U9") (pin "3") (pinfunction "3_3") (pintype "unspecified"))
    )
    (net (code "71") (name "Net-(R34-Pad2)") (class "Default")
      (node (ref "R34") (pin "2") (pinfunction "2_2") (pintype "input"))
      (node (ref "U10") (pin "1") (pinfunction "1_1") (pintype "unspecified"))
    )
    (net (code "72") (name "Net-(R35-Pad1)") (class "Default")
      (node (ref "R35") (pin "1") (pinfunction "1_1") (pintype "input"))
      (node (ref "U10") (pin "3") (pinfunction "3_3") (pintype "unspecified"))
    )
    (net (code "73") (name "Net-(R36-Pad2)") (class "Default")
      (node (ref "R36") (pin "2") (pinfunction "2_2") (pintype "input"))
      (node (ref "U11") (pin "1") (pinfunction "1_1") (pintype "unspecified"))
    )
    (net (code "74") (name "Net-(R37-Pad1)") (class "Default")
      (node (ref "R37") (pin "1") (pinfunction "1_1") (pintype "input"))
      (node (ref "U11") (pin "3") (pinfunction "3_3") (pintype "unspecified"))
    )
    (net (code "75") (name "Net-(R38-Pad2)") (class "Default")
      (node (ref "R38") (pin "2") (pinfunction "2_2") (pintype "input"))
      (node (ref "U12") (pin "1") (pinfunction "1_1") (pintype "unspecified"))
    )
    (net (code "76") (name "Net-(R39-Pad1)") (class "Default")
      (node (ref "R39") (pin "1") (pinfunction "1_1") (pintype "input"))
      (node (ref "U12") (pin "3") (pinfunction "3_3") (pintype "unspecified"))
    )
    (net (code "77") (name "Net-(R40-Pad2)") (class "Default")
      (node (ref "R40") (pin "2") (pinfunction "2_2") (pintype "input"))
      (node (ref "U13") (pin "1") (pinfunction "1_1") (pintype "unspecified"))
    )
    (net (code "78") (name "Net-(R41-Pad1)") (class "Default")
      (node (ref "R41") (pin "1") (pinfunction "1_1") (pintype "input"))
      (node (ref "U13") (pin "3") (pinfunction "3_3") (pintype "unspecified"))
    )
    (net (code "79") (name "Net-(R42-Pad2)") (class "Default")
      (node (ref "R42") (pin "2") (pinfunction "2_2") (pintype "input"))
      (node (ref "U14") (pin "1") (pinfunction "1_1") (pintype "unspecified"))
    )
    (net (code "80") (name "Net-(R43-Pad1)") (class "Default")
      (node (ref "R43") (pin "1") (pinfunction "1_1") (pintype "input"))
      (node (ref "U14") (pin "3") (pinfunction "3_3") (pintype "unspecified"))
    )
    (net (code "81") (name "Net-(R44-Pad2)") (class "Default")
      (node (ref "R44") (pin "2") (pinfunction "2_2") (pintype "input"))
      (node (ref "U15") (pin "1") (pinfunction "1_1") (pintype "unspecified"))
    )
    (net (code "82") (name "Net-(R45-Pad1)") (class "Default")
      (node (ref "R45") (pin "1") (pinfunction "1_1") (pintype "input"))
      (node (ref "U15") (pin "3") (pinfunction "3_3") (pintype "unspecified"))
    )
    (net (code "83") (name "Net-(R46-Pad2)") (class "Default")
      (node (ref "R46") (pin "2") (pinfunction "2_2") (pintype "input"))
      (node (ref "U16") (pin "1") (pinfunction "1_1") (pintype "unspecified"))
    )
    (net (code "84") (name "Net-(R47-Pad1)") (class "Default")
      (node (ref "R47") (pin "1") (pinfunction "1_1") (pintype "input"))
      (node (ref "U16") (pin "3") (pinfunction "3_3") (pintype "unspecified"))
    )
    (net (code "85") (name "Net-(R48-Pad2)") (class "Default")
      (node (ref "R48") (pin "2") (pinfunction "2_2") (pintype "input"))
      (node (ref "U17") (pin "1") (pinfunction "1_1") (pintype "unspecified"))
    )
    (net (code "86") (name "Net-(R49-Pad1)") (class "Default")
      (node (ref "R49") (pin "1") (pinfunction "1_1") (pintype "input"))
      (node (ref "U17") (pin "3") (pinfunction "3_3") (pintype "unspecified"))
    )
    (net (code "87") (name "Net-(R50-Pad2)") (class "Default")
      (node (ref "R50") (pin "2") (pinfunction "2_2") (pintype "input"))
      (node (ref "U18") (pin "1") (pinfunction "1_1") (pintype "unspecified"))
    )
    (net (code "88") (name "Net-(R51-Pad1)") (class "Default")
      (node (ref "R51") (pin "1") (pinfunction "1_1") (pintype "input"))
      (node (ref "U18") (pin "3") (pinfunction "3_3") (pintype "unspecified"))
    )
    (net (code "89") (name "Net-(R52-Pad2)") (class "Default")
      (node (ref "R52") (pin "2") (pinfunction "2_2") (pintype "input"))
      (node (ref "U19") (pin "1") (pinfunction "1_1") (pintype "unspecified"))
    )
    (net (code "90") (name "Net-(R53-Pad1)") (class "Default")
      (node (ref "R53") (pin "1") (pinfunction "1_1") (pintype "input"))
      (node (ref "U19") (pin "3") (pinfunction "3_3") (pintype "unspecified"))
    )
    (net (code "91") (name "Net-(R54-Pad2)") (class "Default")
      (node (ref "R54") (pin "2") (pinfunction "2_2") (pintype "input"))
      (node (ref "U20") (pin "1") (pinfunction "1_1") (pintype "unspecified"))
    )
    (net (code "92") (name "Net-(U1-HR-)") (class "Default")
      (node (ref "R19") (pin "2") (pinfunction "2_2") (pintype "input"))
      (node (ref "U1") (pin "22") (pinfunction "HR-_22") (pintype "unspecified"))
    )
    (net (code "93") (name "Net-(U1-PR-)") (class "Default")
      (node (ref "R10") (pin "2") (pinfunction "2_2") (pintype "input"))
      (node (ref "U1") (pin "20") (pinfunction "PR-_20") (pintype "unspecified"))
    )
    (net (code "94") (name "Net-(U1-V1-)") (class "Default")
      (node (ref "R1") (pin "2") (pinfunction "2_2") (pintype "input"))
      (node (ref "U1") (pin "2") (pinfunction "V1-_2") (pintype "unspecified"))
    )
    (net (code "95") (name "Net-(U1-V2-)") (class "Default")
      (node (ref "R2") (pin "2") (pinfunction "2_2") (pintype "input"))
      (node (ref "U1") (pin "4") (pinfunction "V2-_4") (pintype "unspecified"))
    )
    (net (code "96") (name "Net-(U1-V3-)") (class "Default")
      (node (ref "R3") (pin "2") (pinfunction "2_2") (pintype "input"))
      (node (ref "U1") (pin "6") (pinfunction "V3-_6") (pintype "unspecified"))
    )
    (net (code "97") (name "Net-(U1-V4-)") (class "Default")
      (node (ref "R4") (pin "2") (pinfunction "2_2") (pintype "input"))
      (node (ref "U1") (pin "8") (pinfunction "V4-_8") (pintype "unspecified"))
    )
    (net (code "98") (name "Net-(U1-V5-)") (class "Default")
      (node (ref "R5") (pin "2") (pinfunction "2_2") (pintype "input"))
      (node (ref "U1") (pin "10") (pinfunction "V5-_10") (pintype "unspecified"))
    )
    (net (code "99") (name "Net-(U1-V6-)") (class "Default")
      (node (ref "R6") (pin "2") (pinfunction "2_2") (pintype "input"))
      (node (ref "U1") (pin "12") (pinfunction "V6-_12") (pintype "unspecified"))
    )
    (net (code "100") (name "Net-(U1-V7-)") (class "Default")
      (node (ref "R7") (pin "2") (pinfunction "2_2") (pintype "input"))
      (node (ref "U1") (pin "14") (pinfunction "V7-_14") (pintype "unspecified"))
    )
    (net (code "101") (name "Net-(U1-V8-)") (class "Default")
      (node (ref "R8") (pin "2") (pinfunction "2_2") (pintype "input"))
      (node (ref "U1") (pin "16") (pinfunction "V8-_16") (pintype "unspecified"))
    )
    (net (code "102") (name "Net-(U1-V9-)") (class "Default")
      (node (ref "R9") (pin "2") (pinfunction "2_2") (pintype "input"))
      (node (ref "U1") (pin "18") (pinfunction "V9-_18") (pintype "unspecified"))
    )
    (net (code "103") (name "Net-(U2-SW1+)") (class "Default")
      (node (ref "R11") (pin "2") (pinfunction "2_2") (pintype "input"))
      (node (ref "R12") (pin "1") (pinfunction "1_1") (pintype "input"))
      (node (ref "U2") (pin "1") (pinfunction "SW1+_1") (pintype "unspecified"))
    )
    (net (code "104") (name "Net-(U2-SW2+)") (class "Default")
      (node (ref "R13") (pin "2") (pinfunction "2_2") (pintype "input"))
      (node (ref "R14") (pin "1") (pinfunction "1_1") (pintype "input"))
      (node (ref "U2") (pin "3") (pinfunction "SW2+_3") (pintype "unspecified"))
    )
    (net (code "105") (name "Net-(U2-SW3+)") (class "Default")
      (node (ref "R15") (pin "2") (pinfunction "2_2") (pintype "input"))
      (node (ref "R16") (pin "1") (pinfunction "1_1") (pintype "input"))
      (node (ref "U2") (pin "5") (pinfunction "SW3+_5") (pintype "unspecified"))
    )
    (net (code "106") (name "Net-(U2-SW4+)") (class "Default")
      (node (ref "R17") (pin "2") (pinfunction "2_2") (pintype "input"))
      (node (ref "R18") (pin "1") (pinfunction "1_1") (pintype "input"))
      (node (ref "U2") (pin "7") (pinfunction "SW4+_7") (pintype "unspecified"))
    )
    (net (code "107") (name "Net-(U3-+12V)") (class "Default")
      (node (ref "U3") (pin "1") (pinfunction "+12V_1") (pintype "unspecified"))
      (node (ref "U6") (pin "1") (pinfunction "C_1") (pintype "unspecified"))
    )
    (net (code "108") (name "Net-(U4-D0)") (class "Default")
      (node (ref "U4") (pin "1") (pinfunction "D0_1") (pintype "unspecified"))
      (node (ref "U5") (pin "7") (pinfunction "D0_7") (pintype "unspecified"))
    )
    (net (code "109") (name "Net-(U4-D1)") (class "Default")
      (node (ref "U4") (pin "2") (pinfunction "D1_2") (pintype "unspecified"))
      (node (ref "U5") (pin "8") (pinfunction "D1_8") (pintype "unspecified"))
    )
    (net (code "110") (name "Net-(U4-D2)") (class "Default")
      (node (ref "U4") (pin "3") (pinfunction "D2_3") (pintype "unspecified"))
      (node (ref "U5") (pin "9") (pinfunction "D2_9") (pintype "unspecified"))
    )
    (net (code "111") (name "Net-(U4-D3)") (class "Default")
      (node (ref "U4") (pin "4") (pinfunction "D3_4") (pintype "unspecified"))
      (node (ref "U5") (pin "10") (pinfunction "D3_10") (pintype "unspecified"))
    )
    (net (code "112") (name "Net-(U6-NO)") (class "Default")
      (node (ref "U6") (pin "2") (pinfunction "NO_2") (pintype "unspecified"))
      (node (ref "U8") (pin "2") (pinfunction "Vin_2") (pintype "unspecified"))
    )
    (net (code "113") (name "Net-(U8-Vout)") (class "Default")
      (node (ref "R54") (pin "1") (pinfunction "1_1") (pintype "input"))
      (node (ref "U8") (pin "3") (pinfunction "Vout_3") (pintype "unspecified"))
    )
  )
)
